# DC_DC.net
KiCad netlist of a schematic drawn in Altium Designer
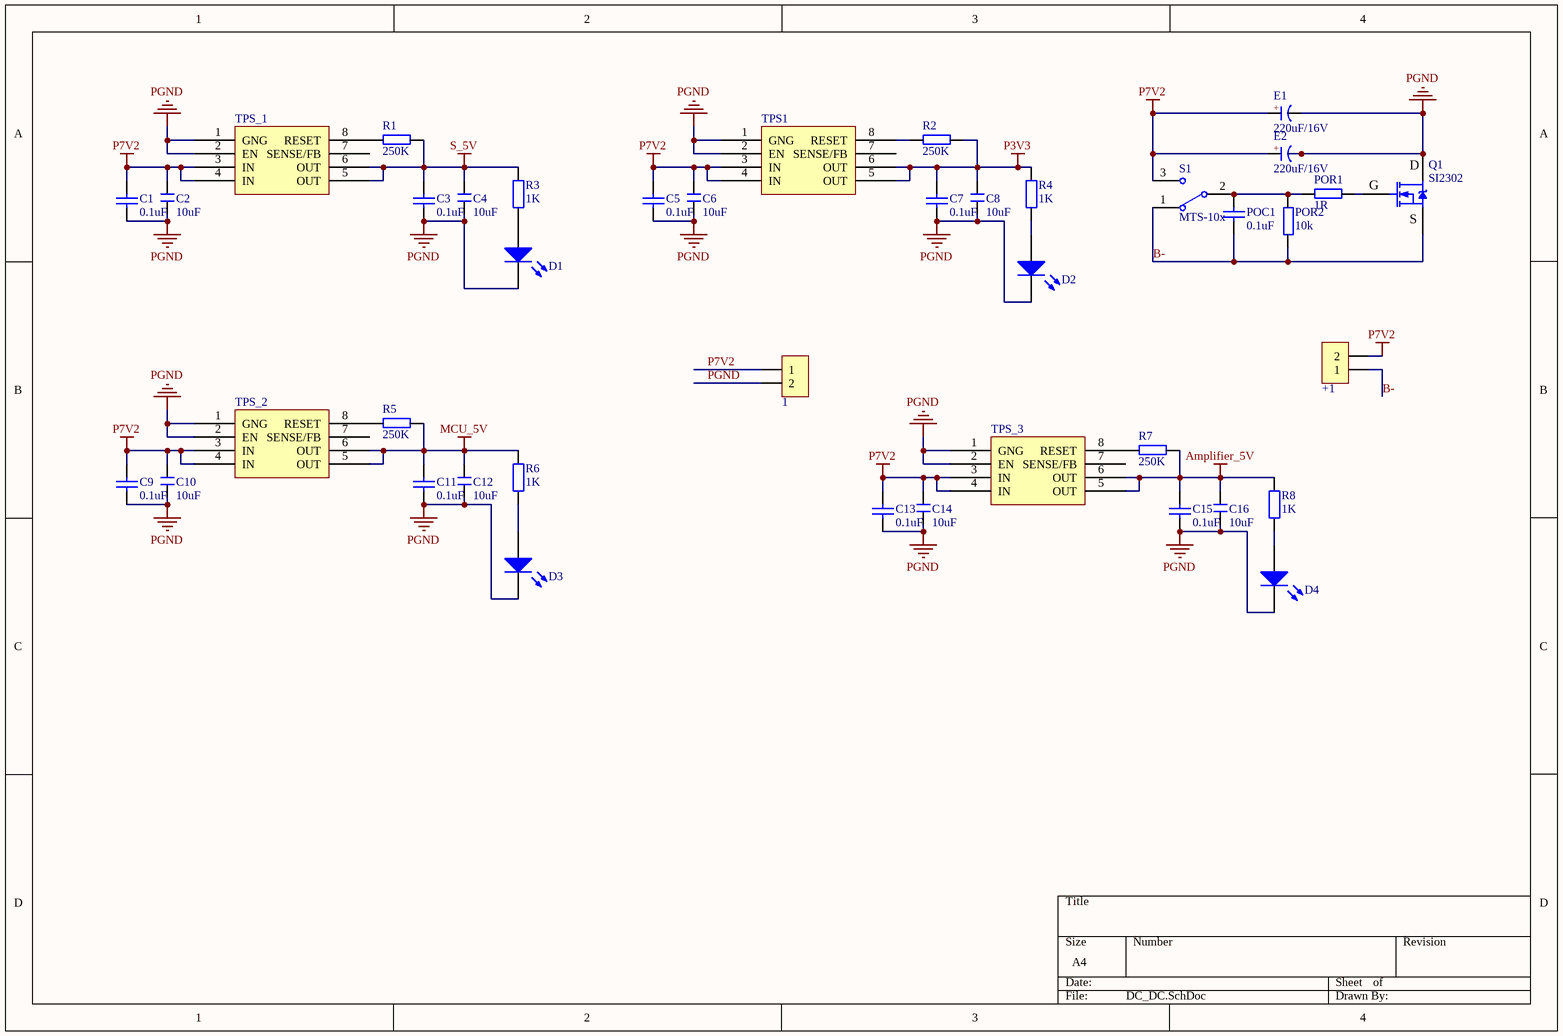
[diagram p0: DC_DC.SchDoc]

(export (version "E")
  (design (tool "Eeschema 10.0.6"))
  (components
    (comp (ref "+1")
      (value "HDR-1X2")
      (footprint "电源入口")
      (description "2P接插件")
      (fields (field (name "版权归属") "封装库来自淘宝 ID：黄晶宝石"))
      (libsource (lib "6.0 - 接插件-脚距5.0") (part "Header 2"))
    )
    (comp (ref "1")
      (value "HDR-1X2")
      (footprint "KF301-5.0-2P")
      (description "2P接插件")
      (fields (field (name "版权归属") "封装库来自淘宝 ID：黄晶宝石"))
      (libsource (lib "") (part "Header 2_1"))
    )
    (comp (ref "C1")
      (value "0.1uF")
      (footprint "C 0603_L")
      (description "Capacitor (Semiconductor SIM Model)")
      (fields (field (name "PUBLISHER") "Altium Limited"))
      (libsource (lib "流光常用") (part "Cap Semi"))
    )
    (comp (ref "C2")
      (value "10uF")
      (footprint "C 0805_L")
      (description "贴片电容")
      (libsource (lib "0.1 - 电阻-电容-电感") (part "C"))
    )
    (comp (ref "C3")
      (value "0.1uF")
      (footprint "C 0603_L")
      (description "Capacitor (Semiconductor SIM Model)")
      (fields (field (name "PUBLISHER") "Altium Limited"))
      (libsource (lib "流光常用") (part "Cap Semi"))
    )
    (comp (ref "C4")
      (value "10uF")
      (footprint "C 0805_L")
      (description "贴片电容")
      (libsource (lib "0.1 - 电阻-电容-电感") (part "C"))
    )
    (comp (ref "C5")
      (value "0.1uF")
      (footprint "C 0603_L")
      (description "Capacitor (Semiconductor SIM Model)")
      (fields (field (name "PUBLISHER") "Altium Limited"))
      (libsource (lib "流光常用") (part "Cap Semi"))
    )
    (comp (ref "C6")
      (value "10uF")
      (footprint "C 0805_L")
      (description "贴片电容")
      (libsource (lib "0.1 - 电阻-电容-电感") (part "C"))
    )
    (comp (ref "C7")
      (value "0.1uF")
      (footprint "C 0603_L")
      (description "Capacitor (Semiconductor SIM Model)")
      (fields (field (name "PUBLISHER") "Altium Limited"))
      (libsource (lib "流光常用") (part "Cap Semi"))
    )
    (comp (ref "C8")
      (value "10uF")
      (footprint "C 0805_L")
      (description "贴片电容")
      (libsource (lib "0.1 - 电阻-电容-电感") (part "C"))
    )
    (comp (ref "C9")
      (value "0.1uF")
      (footprint "C 0603_L")
      (description "Capacitor (Semiconductor SIM Model)")
      (fields (field (name "PUBLISHER") "Altium Limited"))
      (libsource (lib "流光常用") (part "Cap Semi"))
    )
    (comp (ref "C10")
      (value "10uF")
      (footprint "C 0805_L")
      (description "贴片电容")
      (libsource (lib "0.1 - 电阻-电容-电感") (part "C"))
    )
    (comp (ref "C11")
      (value "0.1uF")
      (footprint "C 0603_L")
      (description "Capacitor (Semiconductor SIM Model)")
      (fields (field (name "PUBLISHER") "Altium Limited"))
      (libsource (lib "流光常用") (part "Cap Semi"))
    )
    (comp (ref "C12")
      (value "10uF")
      (footprint "C 0805_L")
      (description "贴片电容")
      (libsource (lib "0.1 - 电阻-电容-电感") (part "C"))
    )
    (comp (ref "C13")
      (value "0.1uF")
      (footprint "C 0603_L")
      (description "Capacitor (Semiconductor SIM Model)")
      (fields (field (name "PUBLISHER") "Altium Limited"))
      (libsource (lib "流光常用") (part "Cap Semi"))
    )
    (comp (ref "C14")
      (value "10uF")
      (footprint "C 0805_L")
      (description "贴片电容")
      (libsource (lib "0.1 - 电阻-电容-电感") (part "C"))
    )
    (comp (ref "C15")
      (value "0.1uF")
      (footprint "C 0603_L")
      (description "Capacitor (Semiconductor SIM Model)")
      (fields (field (name "PUBLISHER") "Altium Limited"))
      (libsource (lib "流光常用") (part "Cap Semi"))
    )
    (comp (ref "C16")
      (value "10uF")
      (footprint "C 0805_L")
      (description "贴片电容")
      (libsource (lib "0.1 - 电阻-电容-电感") (part "C"))
    )
    (comp (ref "D1")
      (value "LED")
      (footprint "LED 0603B")
      (description "发光二极管")
      (libsource (lib "0.3 - LED发光二极管") (part "LED"))
    )
    (comp (ref "D2")
      (value "LED")
      (footprint "LED 0603B")
      (description "发光二极管")
      (libsource (lib "0.3 - LED发光二极管") (part "LED"))
    )
    (comp (ref "D3")
      (value "LED")
      (footprint "LED 0603B")
      (description "发光二极管")
      (libsource (lib "0.3 - LED发光二极管") (part "LED"))
    )
    (comp (ref "D4")
      (value "LED")
      (footprint "LED 0603B")
      (description "发光二极管")
      (libsource (lib "0.3 - LED发光二极管") (part "LED"))
    )
    (comp (ref "E1")
      (value "220uF/16V")
      (footprint "CM D(6.3*7.7)")
      (description "贴片电解电容")
      (libsource (lib "0.1 - 电阻-电容-电感") (part "CE_SMD"))
    )
    (comp (ref "E2")
      (value "220uF/16V")
      (footprint "CM D(6.3*7.7)")
      (description "贴片电解电容")
      (libsource (lib "0.1 - 电阻-电容-电感") (part "CE_SMD"))
    )
    (comp (ref "POC1")
      (value "0.1uF")
      (footprint "C 0603_L")
      (description "Capacitor (Semiconductor SIM Model)")
      (fields (field (name "PUBLISHER") "Altium Limited"))
      (libsource (lib "流光常用") (part "Cap Semi"))
    )
    (comp (ref "POR1") (value "1R") (footprint "R 0603_L") (libsource (lib "8.19lib") (part "R")))
    (comp (ref "POR2") (value "10k") (footprint "C 0603_L") (libsource (lib "8.19lib") (part "R")))
    (comp (ref "Q1")
      (value "SI2302")
      (footprint "TO252 - 3")
      (description "N沟道场效应管")
      (libsource (lib "0.4 - 三极管-场效应管-可控硅") (part "SI2302"))
    )
    (comp (ref "R1") (value "250K") (footprint "R 0603_L") (libsource (lib "8.19lib") (part "R")))
    (comp (ref "R2") (value "250K") (footprint "R 0603_L") (libsource (lib "8.19lib") (part "R")))
    (comp (ref "R3")
      (value "1K")
      (footprint "R 0603_L")
      (description "贴片电阻")
      (libsource (lib "0.1 - 电阻-电容-电感") (part "R"))
    )
    (comp (ref "R4")
      (value "1K")
      (footprint "R 0603_L")
      (description "贴片电阻")
      (libsource (lib "0.1 - 电阻-电容-电感") (part "R"))
    )
    (comp (ref "R5") (value "250K") (footprint "R 0603_L") (libsource (lib "8.19lib") (part "R")))
    (comp (ref "R6")
      (value "1K")
      (footprint "R 0603_L")
      (description "贴片电阻")
      (libsource (lib "0.1 - 电阻-电容-电感") (part "R"))
    )
    (comp (ref "R7") (value "250K") (footprint "R 0603_L") (libsource (lib "8.19lib") (part "R")))
    (comp (ref "R8")
      (value "1K")
      (footprint "R 0603_L")
      (description "贴片电阻")
      (libsource (lib "0.1 - 电阻-电容-电感") (part "R"))
    )
    (comp (ref "S1")
      (value "MTS-10x")
      (footprint "MTS-10x")
      (description "MTS10x系列3脚扭子开关")
      (libsource (lib "0.7 - 常用按键-开关-蜂鸣器-电池") (part "MTS-10x"))
    )
    (comp (ref "TPS1") (value "UUUUUU") (footprint "SOP-8") (libsource (lib "自制模板") (part "TPS7333")))
    (comp (ref "TPS_1") (value "UUUUUU") (footprint "SOP8") (libsource (lib "自制模板") (part "TPS7333")))
    (comp (ref "TPS_2") (value "UUUUUU") (footprint "SOP8") (libsource (lib "自制模板") (part "TPS7333")))
    (comp (ref "TPS_3") (value "UUUUUU") (footprint "SOP8") (libsource (lib "自制模板") (part "TPS7333")))
  )
  (nets
    (net (code "1") (name "/B-") (class "Default")
      (node (ref "+1") (pin "1") (pinfunction "1_1") (pintype "passive"))
      (node (ref "POC1") (pin "1") (pinfunction "1_1") (pintype "passive"))
      (node (ref "POR2") (pin "1") (pintype "passive"))
      (node (ref "Q1") (pin "2") (pinfunction "S_2") (pintype "passive"))
      (node (ref "S1") (pin "1") (pinfunction "1_1") (pintype "passive"))
    )
    (net (code "2") (name "Amplifier_5V") (class "Default")
      (node (ref "C15") (pin "2") (pinfunction "2_2") (pintype "passive"))
      (node (ref "C16") (pin "2") (pinfunction "2_2") (pintype "passive"))
      (node (ref "R7") (pin "1") (pintype "passive"))
      (node (ref "R8") (pin "2") (pinfunction "2_2") (pintype "passive"))
      (node (ref "TPS_3") (pin "5") (pinfunction "OUT_5") (pintype "passive"))
      (node (ref "TPS_3") (pin "6") (pinfunction "OUT_6") (pintype "passive"))
    )
    (net (code "3") (name "MCU_5V") (class "Default")
      (node (ref "C11") (pin "2") (pinfunction "2_2") (pintype "passive"))
      (node (ref "C12") (pin "2") (pinfunction "2_2") (pintype "passive"))
      (node (ref "R5") (pin "1") (pintype "passive"))
      (node (ref "R6") (pin "2") (pinfunction "2_2") (pintype "passive"))
      (node (ref "TPS_2") (pin "5") (pinfunction "OUT_5") (pintype "passive"))
      (node (ref "TPS_2") (pin "6") (pinfunction "OUT_6") (pintype "passive"))
    )
    (net (code "4") (name "Net-(D1-A)") (class "Default")
      (node (ref "D1") (pin "1") (pinfunction "A_1") (pintype "passive"))
      (node (ref "R3") (pin "1") (pinfunction "1_1") (pintype "passive"))
    )
    (net (code "5") (name "Net-(D2-A)") (class "Default")
      (node (ref "D2") (pin "1") (pinfunction "A_1") (pintype "passive"))
      (node (ref "R4") (pin "1") (pinfunction "1_1") (pintype "passive"))
    )
    (net (code "6") (name "Net-(D3-A)") (class "Default")
      (node (ref "D3") (pin "1") (pinfunction "A_1") (pintype "passive"))
      (node (ref "R6") (pin "1") (pinfunction "1_1") (pintype "passive"))
    )
    (net (code "7") (name "Net-(D4-A)") (class "Default")
      (node (ref "D4") (pin "1") (pinfunction "A_1") (pintype "passive"))
      (node (ref "R8") (pin "1") (pinfunction "1_1") (pintype "passive"))
    )
    (net (code "8") (name "Net-(POC1-Pad2)") (class "Default")
      (node (ref "POC1") (pin "2") (pinfunction "2_2") (pintype "passive"))
      (node (ref "POR1") (pin "2") (pintype "passive"))
      (node (ref "POR2") (pin "2") (pintype "passive"))
      (node (ref "S1") (pin "2") (pinfunction "2_2") (pintype "passive"))
    )
    (net (code "9") (name "Net-(Q1-G)") (class "Default")
      (node (ref "POR1") (pin "1") (pintype "passive"))
      (node (ref "Q1") (pin "1") (pinfunction "G_1") (pintype "passive"))
    )
    (net (code "10") (name "Net-(TPS1-RESET)") (class "Default")
      (node (ref "R2") (pin "2") (pintype "passive"))
      (node (ref "TPS1") (pin "8") (pinfunction "RESET_8") (pintype "passive"))
    )
    (net (code "11") (name "Net-(TPS_1-RESET)") (class "Default")
      (node (ref "R1") (pin "2") (pintype "passive"))
      (node (ref "TPS_1") (pin "8") (pinfunction "RESET_8") (pintype "passive"))
    )
    (net (code "12") (name "Net-(TPS_2-RESET)") (class "Default")
      (node (ref "R5") (pin "2") (pintype "passive"))
      (node (ref "TPS_2") (pin "8") (pinfunction "RESET_8") (pintype "passive"))
    )
    (net (code "13") (name "Net-(TPS_3-RESET)") (class "Default")
      (node (ref "R7") (pin "2") (pintype "passive"))
      (node (ref "TPS_3") (pin "8") (pinfunction "RESET_8") (pintype "passive"))
    )
    (net (code "14") (name "P3V3") (class "Default")
      (node (ref "C7") (pin "2") (pinfunction "2_2") (pintype "passive"))
      (node (ref "C8") (pin "2") (pinfunction "2_2") (pintype "passive"))
      (node (ref "R2") (pin "1") (pintype "passive"))
      (node (ref "R4") (pin "2") (pinfunction "2_2") (pintype "passive"))
      (node (ref "TPS1") (pin "5") (pinfunction "OUT_5") (pintype "passive"))
      (node (ref "TPS1") (pin "6") (pinfunction "OUT_6") (pintype "passive"))
    )
    (net (code "15") (name "P7V2") (class "Default")
      (node (ref "+1") (pin "2") (pinfunction "2_2") (pintype "passive"))
      (node (ref "1") (pin "1") (pinfunction "1_1") (pintype "passive"))
      (node (ref "C1") (pin "2") (pinfunction "2_2") (pintype "passive"))
      (node (ref "C10") (pin "2") (pinfunction "2_2") (pintype "passive"))
      (node (ref "C13") (pin "2") (pinfunction "2_2") (pintype "passive"))
      (node (ref "C14") (pin "2") (pinfunction "2_2") (pintype "passive"))
      (node (ref "C2") (pin "2") (pinfunction "2_2") (pintype "passive"))
      (node (ref "C5") (pin "2") (pinfunction "2_2") (pintype "passive"))
      (node (ref "C6") (pin "2") (pinfunction "2_2") (pintype "passive"))
      (node (ref "C9") (pin "2") (pinfunction "2_2") (pintype "passive"))
      (node (ref "E1") (pin "1") (pinfunction "A_1") (pintype "passive"))
      (node (ref "E2") (pin "1") (pinfunction "A_1") (pintype "passive"))
      (node (ref "S1") (pin "3") (pinfunction "3_3") (pintype "passive"))
      (node (ref "TPS1") (pin "3") (pinfunction "IN_3") (pintype "passive"))
      (node (ref "TPS1") (pin "4") (pinfunction "IN_4") (pintype "passive"))
      (node (ref "TPS_1") (pin "3") (pinfunction "IN_3") (pintype "passive"))
      (node (ref "TPS_1") (pin "4") (pinfunction "IN_4") (pintype "passive"))
      (node (ref "TPS_2") (pin "3") (pinfunction "IN_3") (pintype "passive"))
      (node (ref "TPS_2") (pin "4") (pinfunction "IN_4") (pintype "passive"))
      (node (ref "TPS_3") (pin "3") (pinfunction "IN_3") (pintype "passive"))
      (node (ref "TPS_3") (pin "4") (pinfunction "IN_4") (pintype "passive"))
    )
    (net (code "16") (name "PGND") (class "Default")
      (node (ref "1") (pin "2") (pinfunction "2_2") (pintype "passive"))
      (node (ref "C1") (pin "1") (pinfunction "1_1") (pintype "passive"))
      (node (ref "C10") (pin "1") (pinfunction "1_1") (pintype "passive"))
      (node (ref "C11") (pin "1") (pinfunction "1_1") (pintype "passive"))
      (node (ref "C12") (pin "1") (pinfunction "1_1") (pintype "passive"))
      (node (ref "C13") (pin "1") (pinfunction "1_1") (pintype "passive"))
      (node (ref "C14") (pin "1") (pinfunction "1_1") (pintype "passive"))
      (node (ref "C15") (pin "1") (pinfunction "1_1") (pintype "passive"))
      (node (ref "C16") (pin "1") (pinfunction "1_1") (pintype "passive"))
      (node (ref "C2") (pin "1") (pinfunction "1_1") (pintype "passive"))
      (node (ref "C3") (pin "1") (pinfunction "1_1") (pintype "passive"))
      (node (ref "C4") (pin "1") (pinfunction "1_1") (pintype "passive"))
      (node (ref "C5") (pin "1") (pinfunction "1_1") (pintype "passive"))
      (node (ref "C6") (pin "1") (pinfunction "1_1") (pintype "passive"))
      (node (ref "C7") (pin "1") (pinfunction "1_1") (pintype "passive"))
      (node (ref "C8") (pin "1") (pinfunction "1_1") (pintype "passive"))
      (node (ref "C9") (pin "1") (pinfunction "1_1") (pintype "passive"))
      (node (ref "D1") (pin "2") (pinfunction "K_2") (pintype "passive"))
      (node (ref "D2") (pin "2") (pinfunction "K_2") (pintype "passive"))
      (node (ref "D3") (pin "2") (pinfunction "K_2") (pintype "passive"))
      (node (ref "D4") (pin "2") (pinfunction "K_2") (pintype "passive"))
      (node (ref "E1") (pin "2") (pinfunction "K_2") (pintype "passive"))
      (node (ref "E2") (pin "2") (pinfunction "K_2") (pintype "passive"))
      (node (ref "Q1") (pin "3") (pinfunction "D_3") (pintype "passive"))
      (node (ref "TPS1") (pin "1") (pinfunction "GNG_1") (pintype "passive"))
      (node (ref "TPS1") (pin "2") (pinfunction "EN_2") (pintype "passive"))
      (node (ref "TPS_1") (pin "1") (pinfunction "GNG_1") (pintype "passive"))
      (node (ref "TPS_1") (pin "2") (pinfunction "EN_2") (pintype "passive"))
      (node (ref "TPS_2") (pin "1") (pinfunction "GNG_1") (pintype "passive"))
      (node (ref "TPS_2") (pin "2") (pinfunction "EN_2") (pintype "passive"))
      (node (ref "TPS_3") (pin "1") (pinfunction "GNG_1") (pintype "passive"))
      (node (ref "TPS_3") (pin "2") (pinfunction "EN_2") (pintype "passive"))
    )
    (net (code "17") (name "S_5V") (class "Default")
      (node (ref "C3") (pin "2") (pinfunction "2_2") (pintype "passive"))
      (node (ref "C4") (pin "2") (pinfunction "2_2") (pintype "passive"))
      (node (ref "R1") (pin "1") (pintype "passive"))
      (node (ref "R3") (pin "2") (pinfunction "2_2") (pintype "passive"))
      (node (ref "TPS_1") (pin "5") (pinfunction "OUT_5") (pintype "passive"))
      (node (ref "TPS_1") (pin "6") (pinfunction "OUT_6") (pintype "passive"))
    )
    (net (code "18") (name "unconnected-(TPS1-SENSE{slash}FB-Pad7)") (class "Default")
      (node (ref "TPS1") (pin "7") (pinfunction "SENSE/FB_7") (pintype "passive"))
    )
    (net (code "19") (name "unconnected-(TPS_1-SENSE{slash}FB-Pad7)") (class "Default")
      (node (ref "TPS_1") (pin "7") (pinfunction "SENSE/FB_7") (pintype "passive"))
    )
    (net (code "20") (name "unconnected-(TPS_2-SENSE{slash}FB-Pad7)") (class "Default")
      (node (ref "TPS_2") (pin "7") (pinfunction "SENSE/FB_7") (pintype "passive"))
    )
    (net (code "21") (name "unconnected-(TPS_3-SENSE{slash}FB-Pad7)") (class "Default")
      (node (ref "TPS_3") (pin "7") (pinfunction "SENSE/FB_7") (pintype "passive"))
    )
  )
)
